# SCH_NFC-Business-Card_2024-06-21.net
KiCad netlist of a schematic drawn in EasyEDA
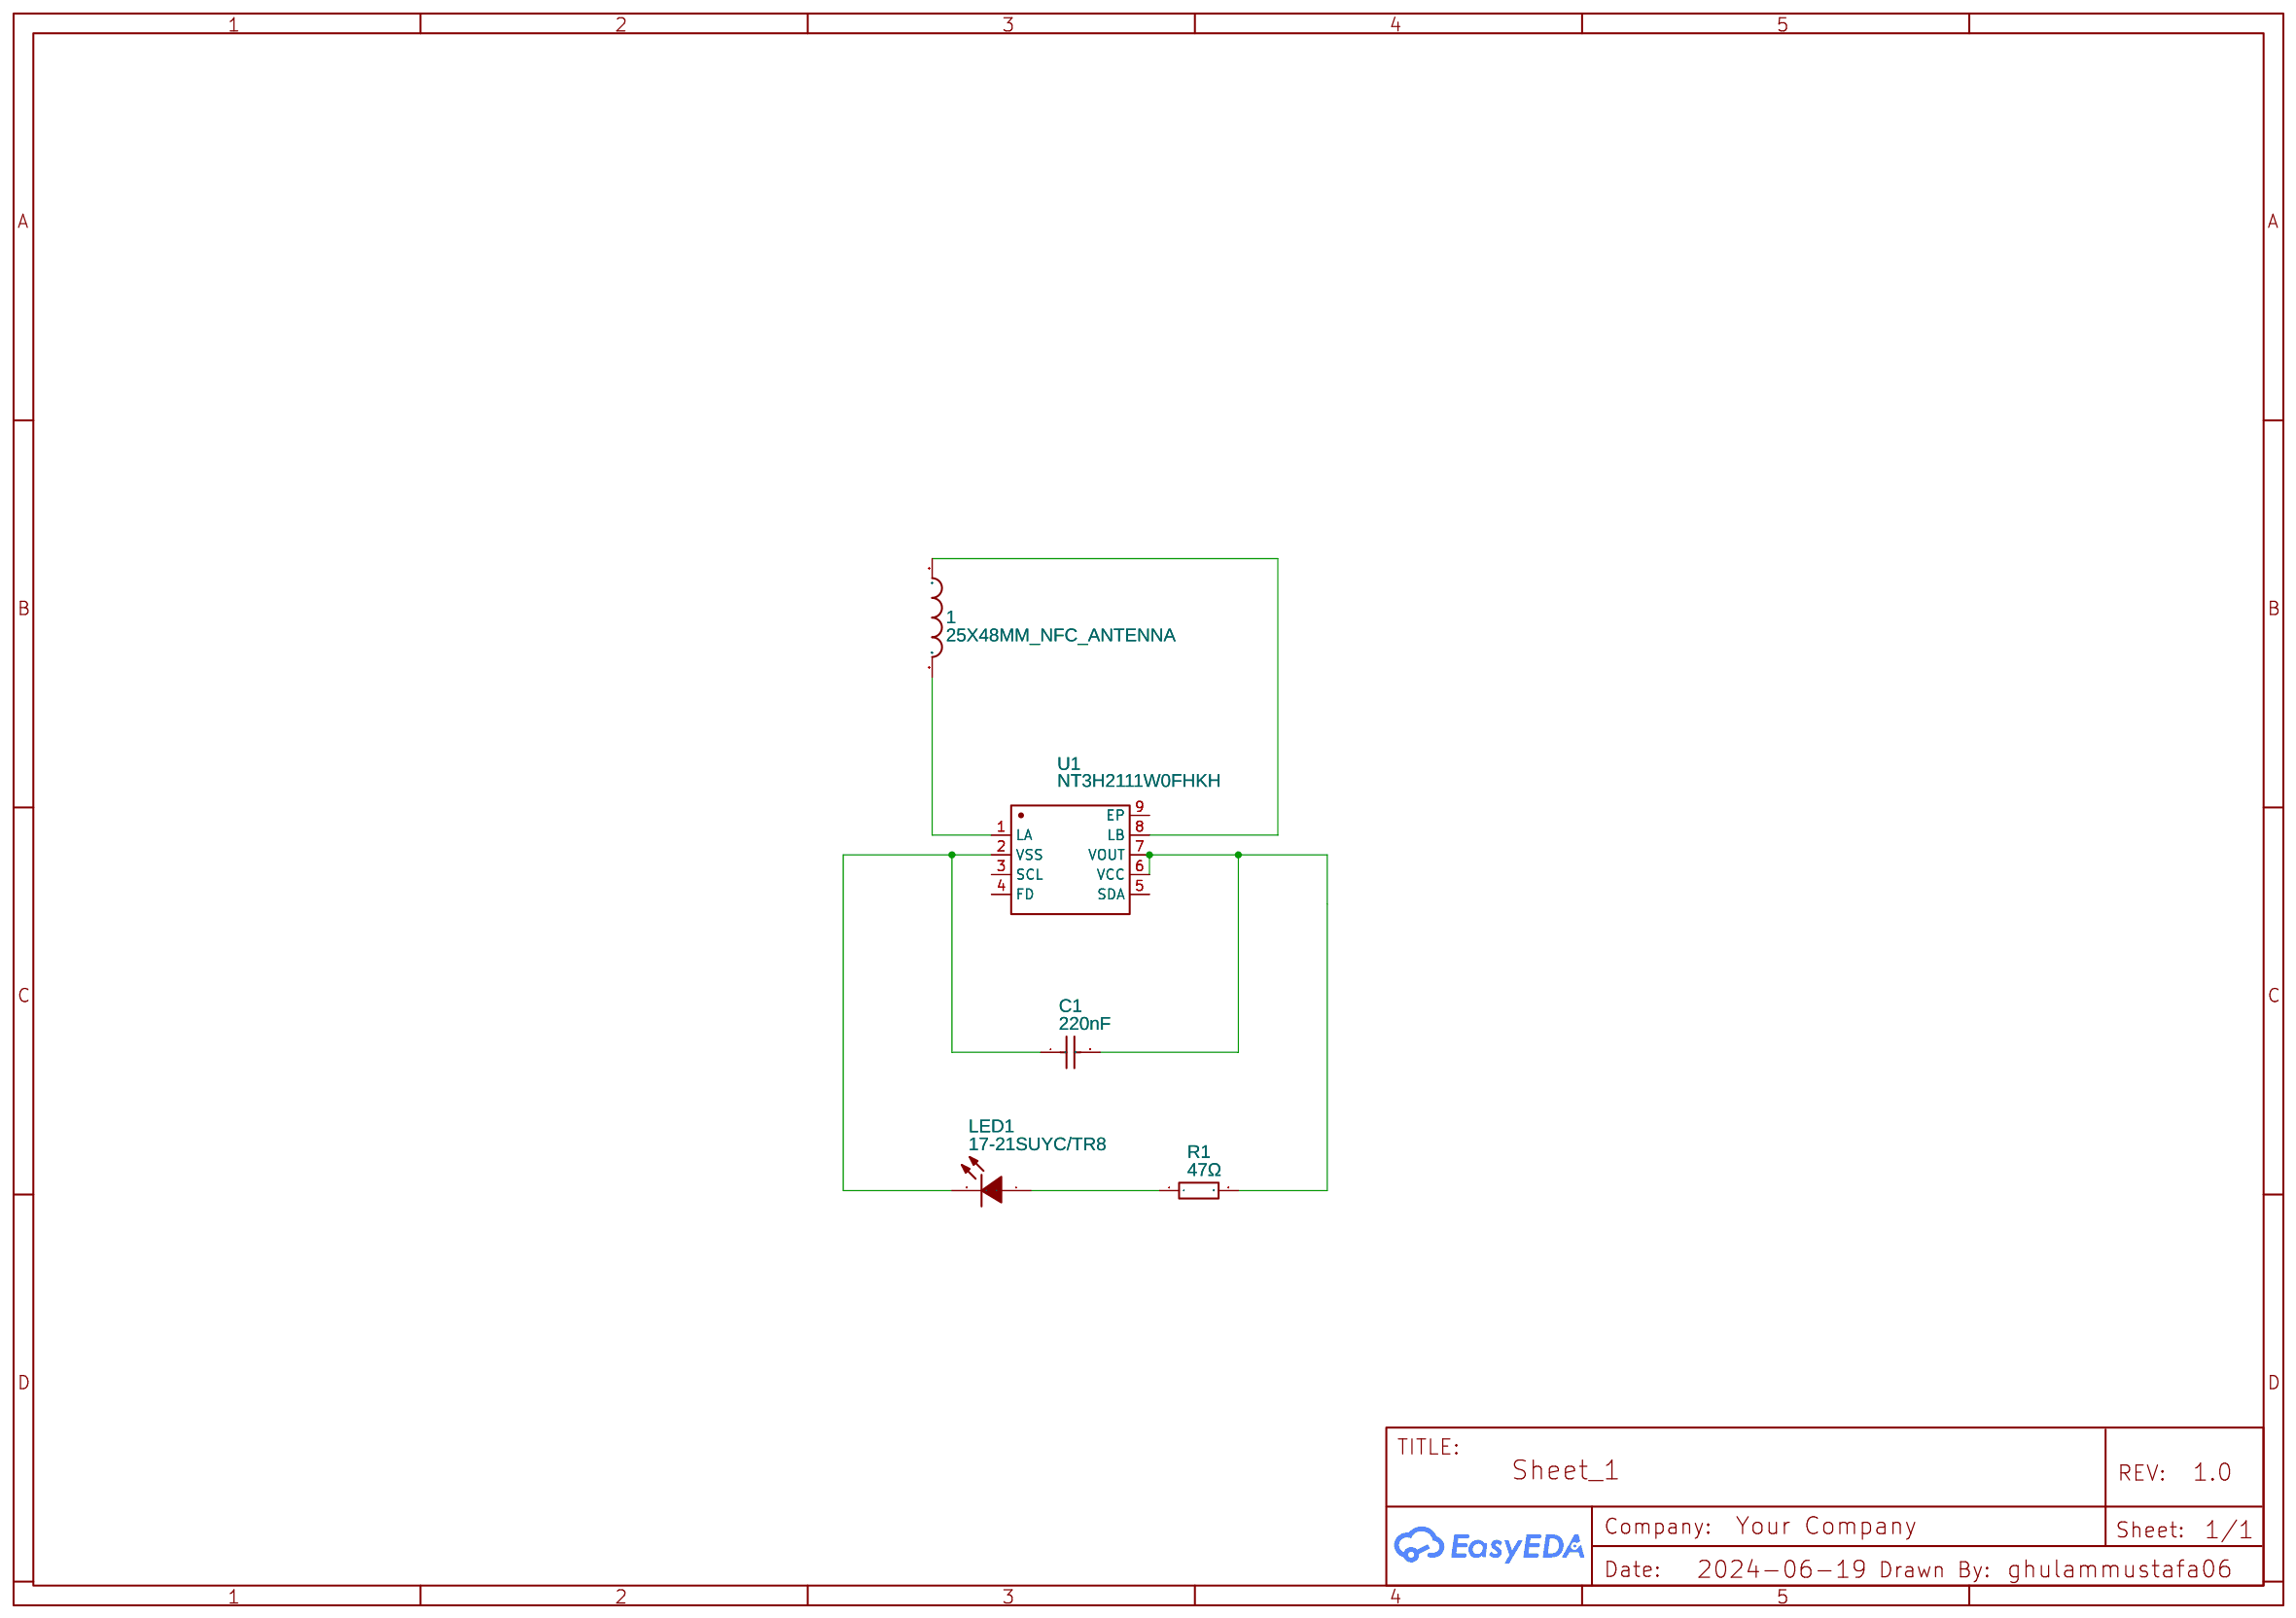
[diagram p0: schematic sheet]

(export (version "E")
  (design (tool "Eeschema 10.0.6"))
  (components
    (comp (ref "1") (value "25X48MM_NFC_ANTENNA") (libsource (lib "") (part "25X48MM_NFC_ANTENNA")))
    (comp (ref "C1")
      (value "220nF")
      (fields
        (field (name "Manufacturer Part") "CL10B224KA8NNNC")
        (field (name "Manufacturer") "SAMSUNG(三星)")
      )
      (libsource (lib "") (part "CL10B224KA8NNNC"))
    )
    (comp (ref "LED1")
      (value "17-21SUYC/TR8")
      (fields (field (name "Manufacturer Part") "KT-0805黄灯") (field (name "Manufacturer") "KENTO"))
      (libsource (lib "") (part "17-21SUYC/TR8"))
    )
    (comp (ref "R1")
      (value "47Ω")
      (fields
        (field (name "Manufacturer Part") "0603WAF470JT5E")
        (field (name "Manufacturer") "UNI-ROYAL(厚声)")
      )
      (libsource (lib "") (part "0603WAF470JT5E"))
    )
    (comp (ref "U1")
      (value "NT3H2111W0FHKH")
      (fields (field (name "Manufacturer") "NXP(恩智浦)"))
      (libsource (lib "") (part "NT3H2111W0FHKH"))
    )
  )
  (nets
    (net (code "1") (name "Net-(LED1-+)") (class "Default")
      (node (ref "LED1") (pin "1") (pinfunction "+_1") (pintype "unspecified"))
      (node (ref "R1") (pin "1") (pinfunction "1_1") (pintype "input"))
    )
    (net (code "2") (name "Net-(LED1--)") (class "Default")
      (node (ref "C1") (pin "1") (pinfunction "1_1") (pintype "input"))
      (node (ref "LED1") (pin "2") (pinfunction "-_2") (pintype "unspecified"))
      (node (ref "U1") (pin "2") (pinfunction "VSS_2") (pintype "unspecified"))
    )
    (net (code "3") (name "Net-(U1-LA)") (class "Default")
      (node (ref "1") (pin "P$2") (pinfunction "P$2_P$2") (pintype "bidirectional"))
      (node (ref "U1") (pin "1") (pinfunction "LA_1") (pintype "unspecified"))
    )
    (net (code "4") (name "Net-(U1-LB)") (class "Default")
      (node (ref "1") (pin "P$1") (pinfunction "P$1_P$1") (pintype "bidirectional"))
      (node (ref "U1") (pin "8") (pinfunction "LB_8") (pintype "unspecified"))
    )
    (net (code "5") (name "Net-(U1-VCC)") (class "Default")
      (node (ref "C1") (pin "2") (pinfunction "2_2") (pintype "input"))
      (node (ref "R1") (pin "2") (pinfunction "2_2") (pintype "input"))
      (node (ref "U1") (pin "6") (pinfunction "VCC_6") (pintype "unspecified"))
      (node (ref "U1") (pin "7") (pinfunction "VOUT_7") (pintype "unspecified"))
    )
    (net (code "6") (name "unconnected-(U1-EP-Pad9)") (class "Default")
      (node (ref "U1") (pin "9") (pinfunction "EP_9") (pintype "unspecified"))
    )
    (net (code "7") (name "unconnected-(U1-FD-Pad4)") (class "Default")
      (node (ref "U1") (pin "4") (pinfunction "FD_4") (pintype "unspecified"))
    )
    (net (code "8") (name "unconnected-(U1-SCL-Pad3)") (class "Default")
      (node (ref "U1") (pin "3") (pinfunction "SCL_3") (pintype "unspecified"))
    )
    (net (code "9") (name "unconnected-(U1-SDA-Pad5)") (class "Default")
      (node (ref "U1") (pin "5") (pinfunction "SDA_5") (pintype "unspecified"))
    )
  )
)
